# Fan_control_hot_air.net
KiCad netlist of a schematic drawn in Altium Designer
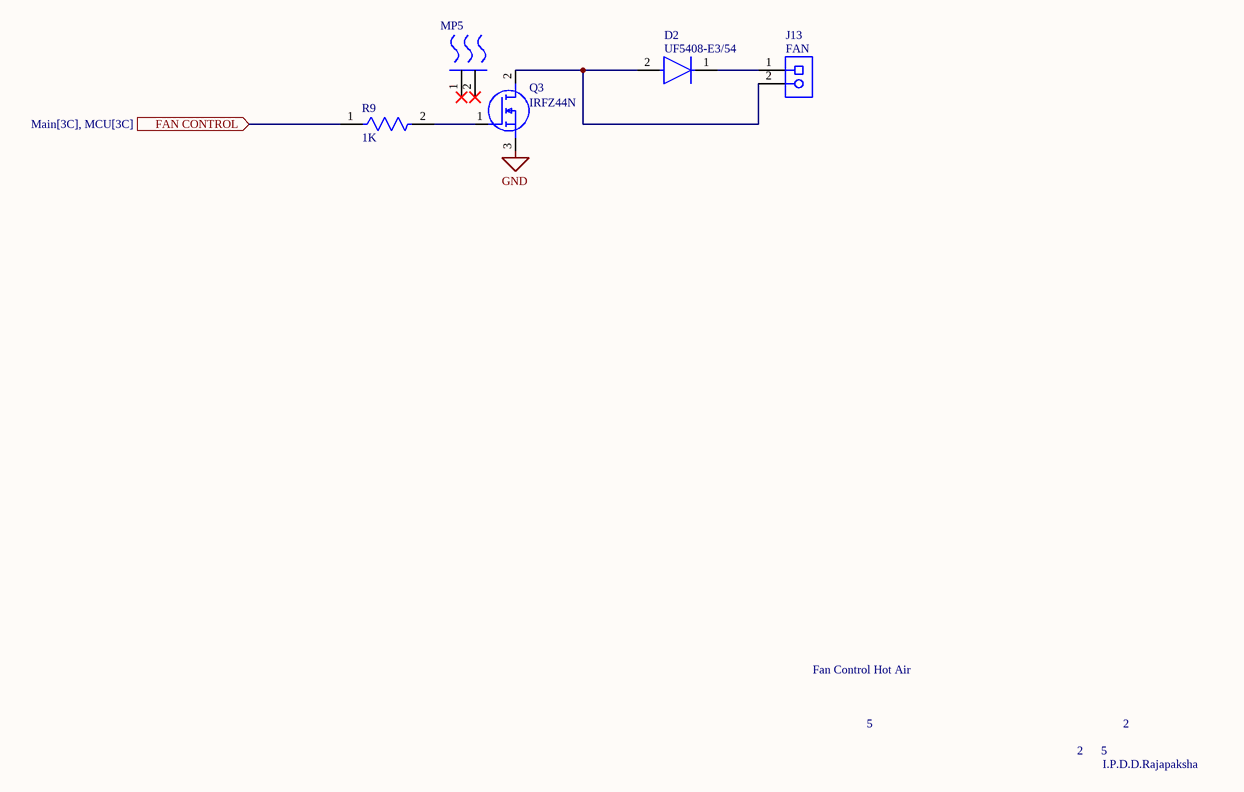
[diagram p0: Fan control hot air.SchDoc]

(export (version "E")
  (design (tool "Eeschema 10.0.6"))
  (components
    (comp (ref "D2")
      (value "UF5408-E3/54")
      (footprint "FP-UF5408-E3-54-MFG")
      (description "DIODE GEN PURP 1KV 3A DO201AD")
      (libsource (lib "Altium Content Vault") (part "d7152d700b627762746794eb795d46e"))
    )
    (comp (ref "J13")
      (value "1729128")
      (footprint "PHOE-1729128-2_V")
      (description "PCB Terminal Block, 13.5 A, 400 V, 2-Pin THD, RoHS, Bulk")
      (fields (field (name "MANUFACTURER") "Phoenix Contact") (field (name "PARAMETER 1") "FAN"))
      (libsource (lib "Altium Content Vault") (part "CN-2P-F-R2"))
    )
    (comp (ref "MP5")
      (value "WV-T264-101E")
      (footprint "FP-WV-T264-101E-MFG")
      (description "HEATSINK W/CLIP FOR TO-264")
      (libsource (lib "Altium Content Vault") (part "df9a98908f0b1072c7a35a179da30c1"))
    )
    (comp (ref "Q3")
      (value "IRFZ44N")
      (footprint "SamacSys:TO254P440X1000X1900-3P")
      (description "MOSFET (N-Channel)")
      (libsource (lib "*") (part "IRFZ44N"))
    )
    (comp (ref "R9")
      (value "1K")
      (footprint "FP-CMF50-0")
      (description "CMF5073K200FHEB Res Metal Film 73.2K Ohm 1% 0.125W(1/8W) ±50ppm/°C Epoxy AXL T/R")
      (fields (field (name "TOLERANCE") "1%") (field (name "Comment") "CMF5073K200FHEB"))
      (libsource (lib "Altium Content Vault") (part "1029c3af85768c4190bb7ad29bc67b5"))
    )
  )
  (nets
    (net (code "1") (name "/FAN CONTROL") (class "Default")
      (node (ref "R9") (pin "1") (pinfunction "1_1") (pintype "passive"))
    )
    (net (code "2") (name "GND") (class "Default")
      (node (ref "Q3") (pin "3") (pinfunction "S_3") (pintype "passive"))
    )
    (net (code "3") (name "Net-(D2-A)") (class "Default")
      (node (ref "D2") (pin "2") (pinfunction "A_2") (pintype "passive"))
      (node (ref "J13") (pin "2") (pinfunction "2_2") (pintype "passive"))
      (node (ref "Q3") (pin "2") (pinfunction "D_2") (pintype "passive"))
    )
    (net (code "4") (name "Net-(D2-C)") (class "Default")
      (node (ref "D2") (pin "1") (pinfunction "C_1") (pintype "passive"))
      (node (ref "J13") (pin "1") (pinfunction "1_1") (pintype "passive"))
    )
    (net (code "5") (name "Net-(Q3-G)") (class "Default")
      (node (ref "Q3") (pin "1") (pinfunction "G_1") (pintype "passive"))
      (node (ref "R9") (pin "2") (pinfunction "2_2") (pintype "passive"))
    )
    (net (code "6") (name "unconnected-(MP5-MNT_1-Pad1)") (class "Default")
      (node (ref "MP5") (pin "1") (pinfunction "MNT_1_1") (pintype "passive+no_connect"))
    )
    (net (code "7") (name "unconnected-(MP5-MNT_2-Pad2)") (class "Default")
      (node (ref "MP5") (pin "2") (pinfunction "MNT_2_2") (pintype "passive+no_connect"))
    )
  )
)
